# sensor_garis.net
KiCad netlist of a schematic drawn in EAGLE
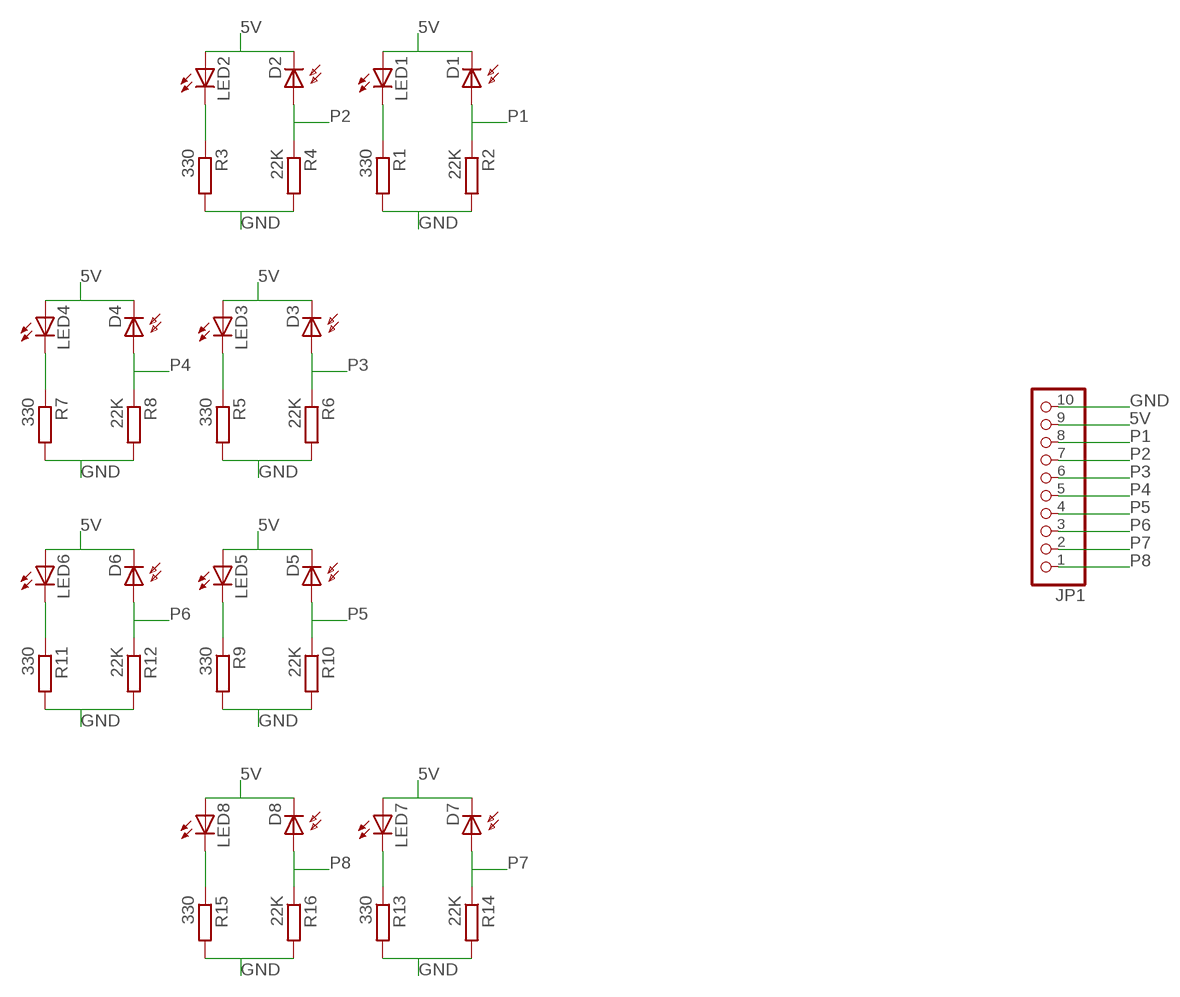
[diagram p0: schematic, sheet 1]

(export (version "E")
  (design (tool "Eeschema 10.0.6"))
  (components
    (comp (ref "D1")
      (value "BPX65")
      (footprint "eagle-import:BPX65")
      (fields (field (name "MPN") "BPX65."))
      (libsource (lib "eagle-import") (part "BPX65"))
    )
    (comp (ref "D2")
      (value "BPX65")
      (footprint "eagle-import:BPX65")
      (fields (field (name "MPN") "BPX65."))
      (libsource (lib "eagle-import") (part "BPX65"))
    )
    (comp (ref "D3")
      (value "BPX65")
      (footprint "eagle-import:BPX65")
      (fields (field (name "MPN") "BPX65."))
      (libsource (lib "eagle-import") (part "BPX65"))
    )
    (comp (ref "D4")
      (value "BPX65")
      (footprint "eagle-import:BPX65")
      (fields (field (name "MPN") "BPX65."))
      (libsource (lib "eagle-import") (part "BPX65"))
    )
    (comp (ref "D5")
      (value "BPX65")
      (footprint "eagle-import:BPX65")
      (fields (field (name "MPN") "BPX65."))
      (libsource (lib "eagle-import") (part "BPX65"))
    )
    (comp (ref "D6")
      (value "BPX65")
      (footprint "eagle-import:BPX65")
      (fields (field (name "MPN") "BPX65."))
      (libsource (lib "eagle-import") (part "BPX65"))
    )
    (comp (ref "D7")
      (value "BPX65")
      (footprint "eagle-import:BPX65")
      (fields (field (name "MPN") "BPX65."))
      (libsource (lib "eagle-import") (part "BPX65"))
    )
    (comp (ref "D8")
      (value "BPX65")
      (footprint "eagle-import:BPX65")
      (fields (field (name "MPN") "BPX65."))
      (libsource (lib "eagle-import") (part "BPX65"))
    )
    (comp (ref "JP1")
      (value "PINHD-1X10")
      (footprint "eagle-import:1X10")
      (libsource (lib "eagle-import") (part "PINHD-1X10"))
    )
    (comp (ref "LED1")
      (value "LED3MM")
      (footprint "eagle-import:LED3MM")
      (libsource (lib "eagle-import") (part "LED3MM"))
    )
    (comp (ref "LED2")
      (value "LED3MM")
      (footprint "eagle-import:LED3MM")
      (libsource (lib "eagle-import") (part "LED3MM"))
    )
    (comp (ref "LED3")
      (value "LED3MM")
      (footprint "eagle-import:LED3MM")
      (libsource (lib "eagle-import") (part "LED3MM"))
    )
    (comp (ref "LED4")
      (value "LED3MM")
      (footprint "eagle-import:LED3MM")
      (libsource (lib "eagle-import") (part "LED3MM"))
    )
    (comp (ref "LED5")
      (value "LED3MM")
      (footprint "eagle-import:LED3MM")
      (libsource (lib "eagle-import") (part "LED3MM"))
    )
    (comp (ref "LED6")
      (value "LED3MM")
      (footprint "eagle-import:LED3MM")
      (libsource (lib "eagle-import") (part "LED3MM"))
    )
    (comp (ref "LED7")
      (value "LED3MM")
      (footprint "eagle-import:LED3MM")
      (libsource (lib "eagle-import") (part "LED3MM"))
    )
    (comp (ref "LED8")
      (value "LED3MM")
      (footprint "eagle-import:LED3MM")
      (libsource (lib "eagle-import") (part "LED3MM"))
    )
    (comp (ref "R1")
      (value "330")
      (footprint "eagle-import:0207_7")
      (libsource (lib "eagle-import") (part "R-EU_0207/7"))
    )
    (comp (ref "R2")
      (value "22K")
      (footprint "eagle-import:0207_7")
      (libsource (lib "eagle-import") (part "R-EU_0207/7"))
    )
    (comp (ref "R3")
      (value "330")
      (footprint "eagle-import:0207_7")
      (libsource (lib "eagle-import") (part "R-EU_0207/7"))
    )
    (comp (ref "R4")
      (value "22K")
      (footprint "eagle-import:0207_7")
      (libsource (lib "eagle-import") (part "R-EU_0207/7"))
    )
    (comp (ref "R5")
      (value "330")
      (footprint "eagle-import:0207_7")
      (libsource (lib "eagle-import") (part "R-EU_0207/7"))
    )
    (comp (ref "R6")
      (value "22K")
      (footprint "eagle-import:0207_7")
      (libsource (lib "eagle-import") (part "R-EU_0207/7"))
    )
    (comp (ref "R7")
      (value "330")
      (footprint "eagle-import:0207_7")
      (libsource (lib "eagle-import") (part "R-EU_0207/7"))
    )
    (comp (ref "R8")
      (value "22K")
      (footprint "eagle-import:0207_7")
      (libsource (lib "eagle-import") (part "R-EU_0207/7"))
    )
    (comp (ref "R9")
      (value "330")
      (footprint "eagle-import:0207_7")
      (libsource (lib "eagle-import") (part "R-EU_0207/7"))
    )
    (comp (ref "R10")
      (value "22K")
      (footprint "eagle-import:0207_7")
      (libsource (lib "eagle-import") (part "R-EU_0207/7"))
    )
    (comp (ref "R11")
      (value "330")
      (footprint "eagle-import:0207_7")
      (libsource (lib "eagle-import") (part "R-EU_0207/7"))
    )
    (comp (ref "R12")
      (value "22K")
      (footprint "eagle-import:0207_7")
      (libsource (lib "eagle-import") (part "R-EU_0207/7"))
    )
    (comp (ref "R13")
      (value "330")
      (footprint "eagle-import:0207_7")
      (libsource (lib "eagle-import") (part "R-EU_0207/7"))
    )
    (comp (ref "R14")
      (value "22K")
      (footprint "eagle-import:0207_7")
      (libsource (lib "eagle-import") (part "R-EU_0207/7"))
    )
    (comp (ref "R15")
      (value "330")
      (footprint "eagle-import:0207_7")
      (libsource (lib "eagle-import") (part "R-EU_0207/7"))
    )
    (comp (ref "R16")
      (value "22K")
      (footprint "eagle-import:0207_7")
      (libsource (lib "eagle-import") (part "R-EU_0207/7"))
    )
  )
  (nets
    (net (code "1") (name "/5V") (class "Default")
      (node (ref "D1") (pin "K") (pinfunction "C_K") (pintype "passive"))
      (node (ref "D2") (pin "K") (pinfunction "C_K") (pintype "passive"))
      (node (ref "D3") (pin "K") (pinfunction "C_K") (pintype "passive"))
      (node (ref "D4") (pin "K") (pinfunction "C_K") (pintype "passive"))
      (node (ref "D5") (pin "K") (pinfunction "C_K") (pintype "passive"))
      (node (ref "D6") (pin "K") (pinfunction "C_K") (pintype "passive"))
      (node (ref "D7") (pin "K") (pinfunction "C_K") (pintype "passive"))
      (node (ref "D8") (pin "K") (pinfunction "C_K") (pintype "passive"))
      (node (ref "JP1") (pin "9") (pinfunction "9_9") (pintype "passive"))
      (node (ref "LED1") (pin "A") (pinfunction "A_A") (pintype "passive"))
      (node (ref "LED2") (pin "A") (pinfunction "A_A") (pintype "passive"))
      (node (ref "LED3") (pin "A") (pinfunction "A_A") (pintype "passive"))
      (node (ref "LED4") (pin "A") (pinfunction "A_A") (pintype "passive"))
      (node (ref "LED5") (pin "A") (pinfunction "A_A") (pintype "passive"))
      (node (ref "LED6") (pin "A") (pinfunction "A_A") (pintype "passive"))
      (node (ref "LED7") (pin "A") (pinfunction "A_A") (pintype "passive"))
      (node (ref "LED8") (pin "A") (pinfunction "A_A") (pintype "passive"))
    )
    (net (code "2") (name "/GND") (class "Default")
      (node (ref "JP1") (pin "10") (pinfunction "10_10") (pintype "passive"))
      (node (ref "R1") (pin "2") (pinfunction "2_2") (pintype "passive"))
      (node (ref "R10") (pin "2") (pinfunction "2_2") (pintype "passive"))
      (node (ref "R11") (pin "2") (pinfunction "2_2") (pintype "passive"))
      (node (ref "R12") (pin "2") (pinfunction "2_2") (pintype "passive"))
      (node (ref "R13") (pin "2") (pinfunction "2_2") (pintype "passive"))
      (node (ref "R14") (pin "2") (pinfunction "2_2") (pintype "passive"))
      (node (ref "R15") (pin "2") (pinfunction "2_2") (pintype "passive"))
      (node (ref "R16") (pin "2") (pinfunction "2_2") (pintype "passive"))
      (node (ref "R2") (pin "2") (pinfunction "2_2") (pintype "passive"))
      (node (ref "R3") (pin "2") (pinfunction "2_2") (pintype "passive"))
      (node (ref "R4") (pin "2") (pinfunction "2_2") (pintype "passive"))
      (node (ref "R5") (pin "2") (pinfunction "2_2") (pintype "passive"))
      (node (ref "R6") (pin "2") (pinfunction "2_2") (pintype "passive"))
      (node (ref "R7") (pin "2") (pinfunction "2_2") (pintype "passive"))
      (node (ref "R8") (pin "2") (pinfunction "2_2") (pintype "passive"))
      (node (ref "R9") (pin "2") (pinfunction "2_2") (pintype "passive"))
    )
    (net (code "3") (name "/P1") (class "Default")
      (node (ref "D1") (pin "A") (pinfunction "A_A") (pintype "passive"))
      (node (ref "JP1") (pin "8") (pinfunction "8_8") (pintype "passive"))
      (node (ref "R2") (pin "1") (pinfunction "1_1") (pintype "passive"))
    )
    (net (code "4") (name "/P2") (class "Default")
      (node (ref "D2") (pin "A") (pinfunction "A_A") (pintype "passive"))
      (node (ref "JP1") (pin "7") (pinfunction "7_7") (pintype "passive"))
      (node (ref "R4") (pin "1") (pinfunction "1_1") (pintype "passive"))
    )
    (net (code "5") (name "/P3") (class "Default")
      (node (ref "D3") (pin "A") (pinfunction "A_A") (pintype "passive"))
      (node (ref "JP1") (pin "6") (pinfunction "6_6") (pintype "passive"))
      (node (ref "R6") (pin "1") (pinfunction "1_1") (pintype "passive"))
    )
    (net (code "6") (name "/P4") (class "Default")
      (node (ref "D4") (pin "A") (pinfunction "A_A") (pintype "passive"))
      (node (ref "JP1") (pin "5") (pinfunction "5_5") (pintype "passive"))
      (node (ref "R8") (pin "1") (pinfunction "1_1") (pintype "passive"))
    )
    (net (code "7") (name "/P5") (class "Default")
      (node (ref "D5") (pin "A") (pinfunction "A_A") (pintype "passive"))
      (node (ref "JP1") (pin "4") (pinfunction "4_4") (pintype "passive"))
      (node (ref "R10") (pin "1") (pinfunction "1_1") (pintype "passive"))
    )
    (net (code "8") (name "/P6") (class "Default")
      (node (ref "D6") (pin "A") (pinfunction "A_A") (pintype "passive"))
      (node (ref "JP1") (pin "3") (pinfunction "3_3") (pintype "passive"))
      (node (ref "R12") (pin "1") (pinfunction "1_1") (pintype "passive"))
    )
    (net (code "9") (name "/P7") (class "Default")
      (node (ref "D7") (pin "A") (pinfunction "A_A") (pintype "passive"))
      (node (ref "JP1") (pin "2") (pinfunction "2_2") (pintype "passive"))
      (node (ref "R14") (pin "1") (pinfunction "1_1") (pintype "passive"))
    )
    (net (code "10") (name "/P8") (class "Default")
      (node (ref "D8") (pin "A") (pinfunction "A_A") (pintype "passive"))
      (node (ref "JP1") (pin "1") (pinfunction "1_1") (pintype "passive"))
      (node (ref "R16") (pin "1") (pinfunction "1_1") (pintype "passive"))
    )
    (net (code "11") (name "Net-(LED1-C)") (class "Default")
      (node (ref "LED1") (pin "K") (pinfunction "C_K") (pintype "passive"))
      (node (ref "R1") (pin "1") (pinfunction "1_1") (pintype "passive"))
    )
    (net (code "12") (name "Net-(LED2-C)") (class "Default")
      (node (ref "LED2") (pin "K") (pinfunction "C_K") (pintype "passive"))
      (node (ref "R3") (pin "1") (pinfunction "1_1") (pintype "passive"))
    )
    (net (code "13") (name "Net-(LED3-C)") (class "Default")
      (node (ref "LED3") (pin "K") (pinfunction "C_K") (pintype "passive"))
      (node (ref "R5") (pin "1") (pinfunction "1_1") (pintype "passive"))
    )
    (net (code "14") (name "Net-(LED4-C)") (class "Default")
      (node (ref "LED4") (pin "K") (pinfunction "C_K") (pintype "passive"))
      (node (ref "R7") (pin "1") (pinfunction "1_1") (pintype "passive"))
    )
    (net (code "15") (name "Net-(LED5-C)") (class "Default")
      (node (ref "LED5") (pin "K") (pinfunction "C_K") (pintype "passive"))
      (node (ref "R9") (pin "1") (pinfunction "1_1") (pintype "passive"))
    )
    (net (code "16") (name "Net-(LED6-C)") (class "Default")
      (node (ref "LED6") (pin "K") (pinfunction "C_K") (pintype "passive"))
      (node (ref "R11") (pin "1") (pinfunction "1_1") (pintype "passive"))
    )
    (net (code "17") (name "Net-(LED7-C)") (class "Default")
      (node (ref "LED7") (pin "K") (pinfunction "C_K") (pintype "passive"))
      (node (ref "R13") (pin "1") (pinfunction "1_1") (pintype "passive"))
    )
    (net (code "18") (name "Net-(LED8-C)") (class "Default")
      (node (ref "LED8") (pin "K") (pinfunction "C_K") (pintype "passive"))
      (node (ref "R15") (pin "1") (pinfunction "1_1") (pintype "passive"))
    )
  )
)
